# BrauV2_IOController.net
KiCad netlist of a schematic drawn in Altium Designer
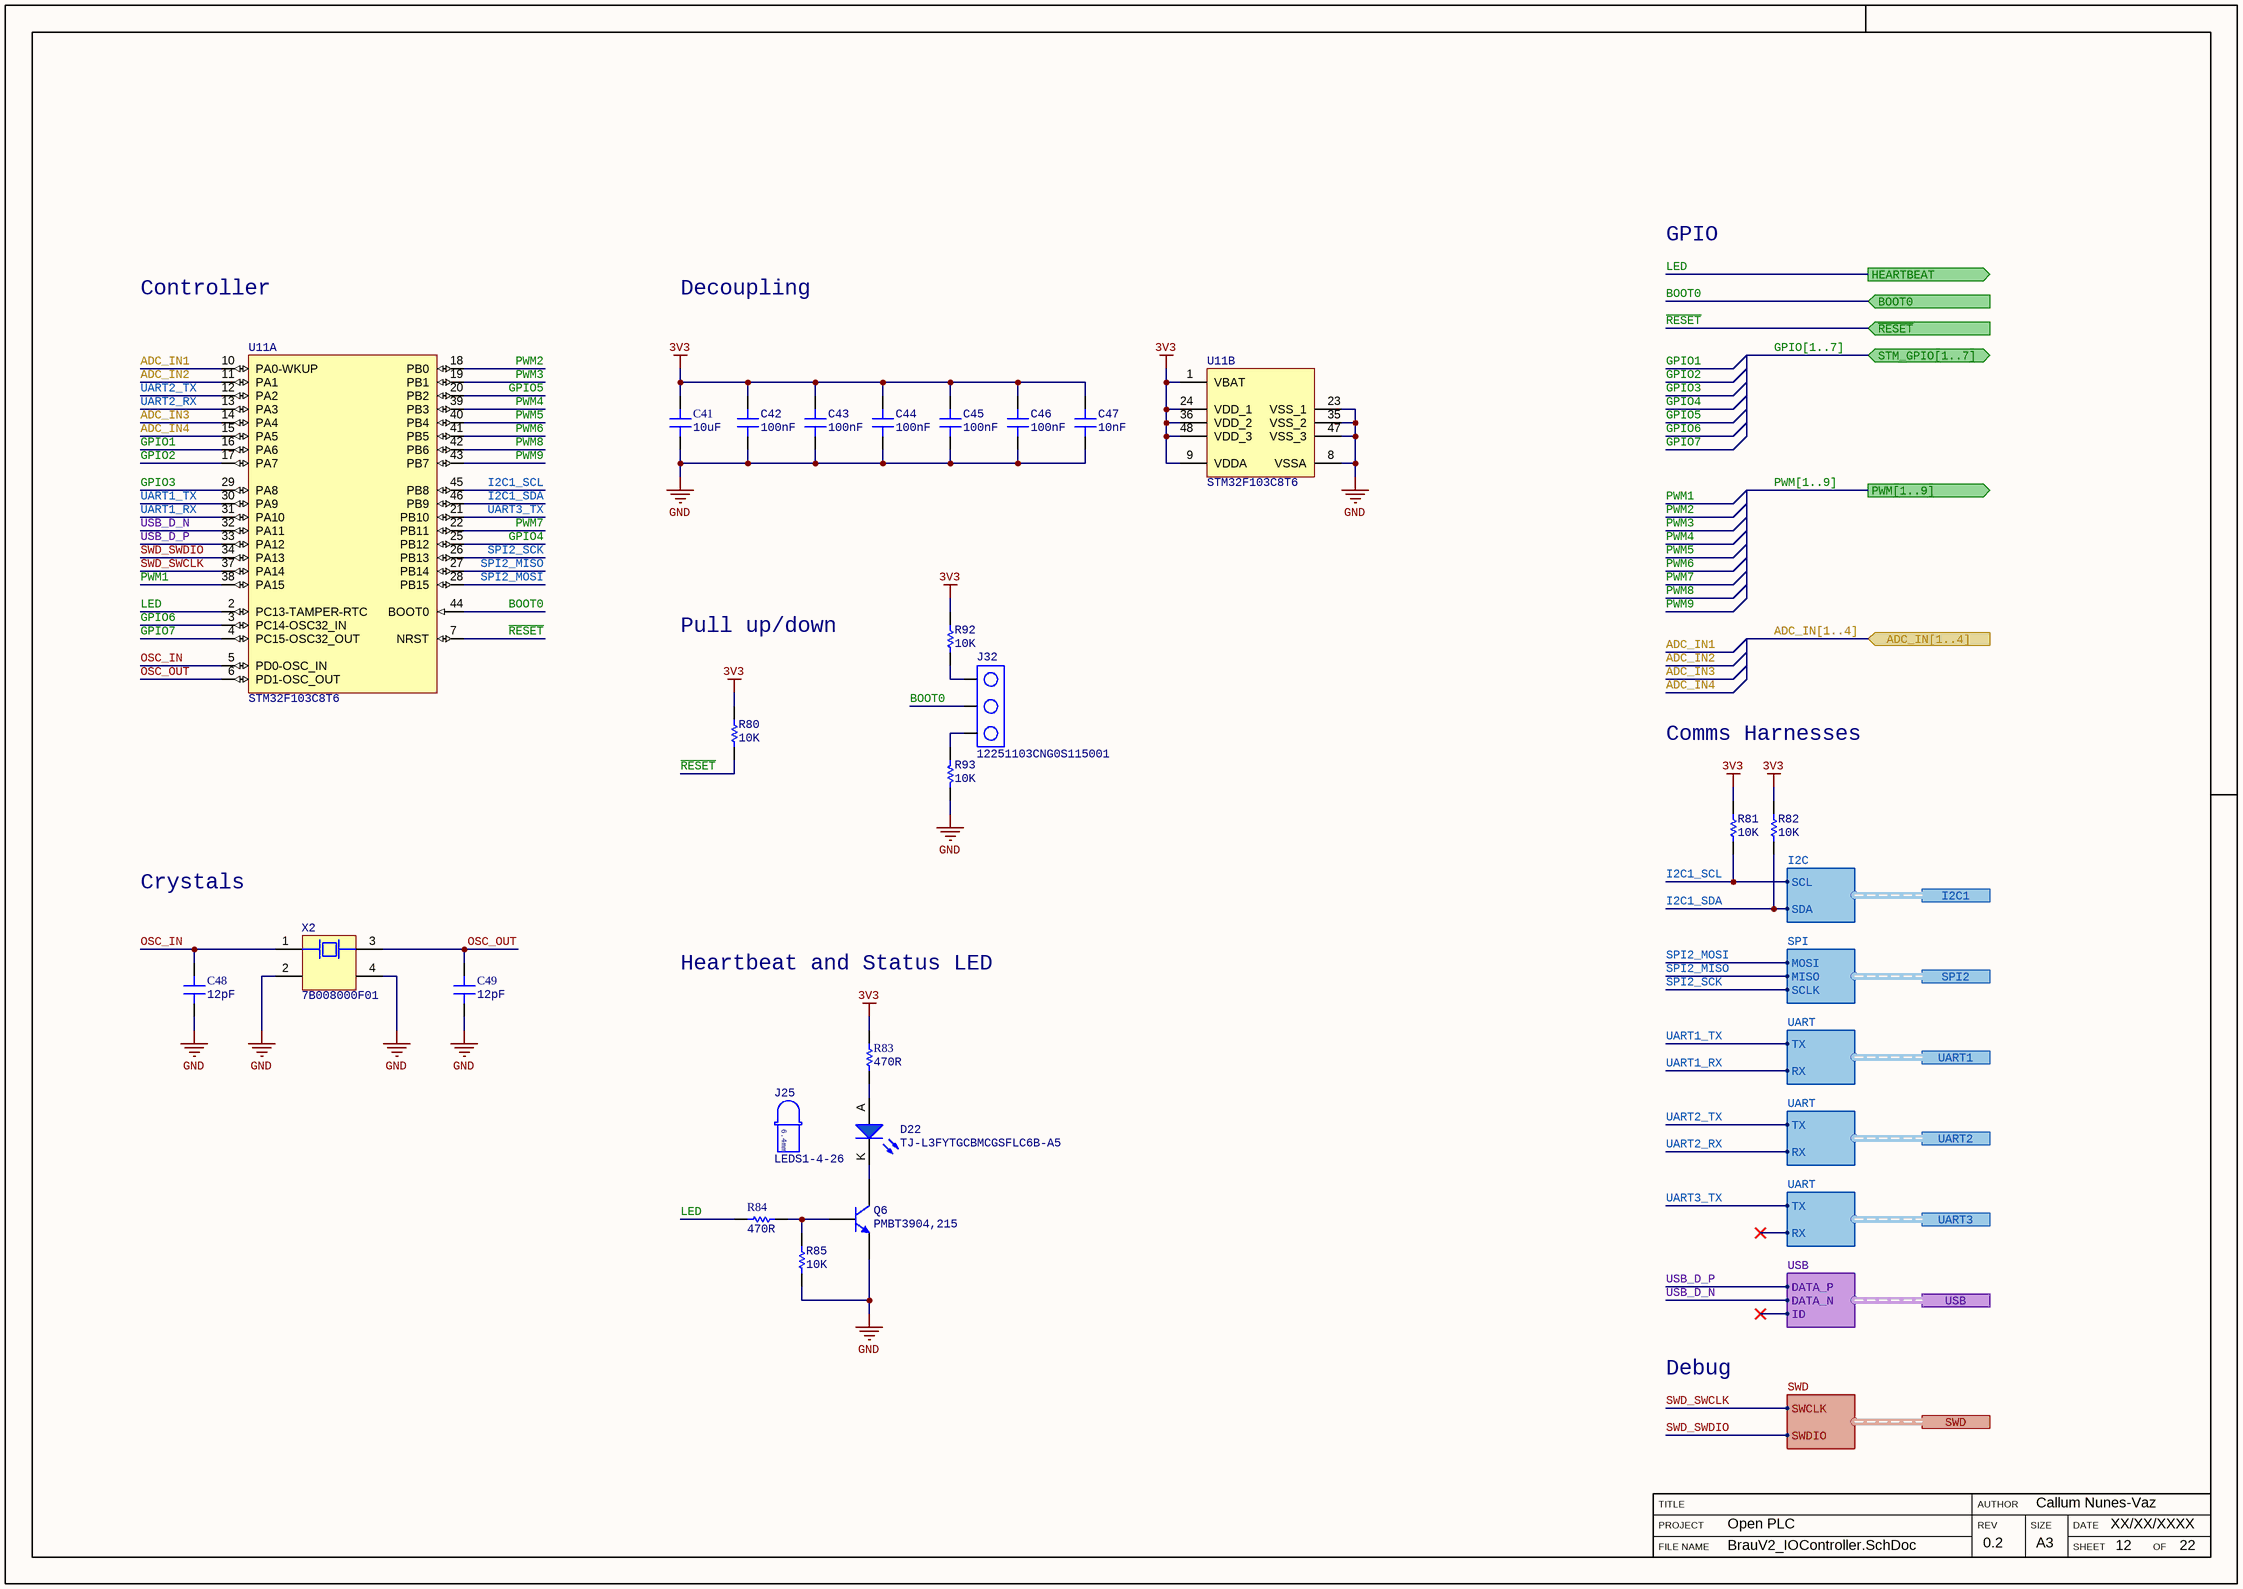
[diagram p0: BrauV2_IOController.SchDoc]

(export (version "E")
  (design (tool "Eeschema 10.0.6"))
  (components
    (comp (ref "C41")
      (value "CC1206KKX5R9BB106")
      (footprint "SMD_CAP_1206(3216)_N")
      (description "10uF ±10% 50V X5R 1206 Multilayer Ceramic Capacitors MLCC - SMD/SMT RoHS")
      (fields (field (name "TOLERANCE") "10%") (field (name "CAPACITANCE") "10uF"))
      (libsource (lib "BrauV2_Capacitor") (part "10uF 1206 50V 10%"))
    )
    (comp (ref "C42")
      (value "CC0402KRX5R6BB104")
      (footprint "SMD_CAP_0402(1005)_N")
      (description "100nF ±10% 10V X5R 0402 Multilayer Ceramic Capacitors MLCC - SMD/SMT RoHS")
      (fields (field (name "TOLERANCE") "10%") (field (name "CAPACITANCE") "100nF"))
      (libsource (lib "BrauV2_Capacitor") (part "100nF 0402 10V 10%"))
    )
    (comp (ref "C43")
      (value "CC0402KRX5R6BB104")
      (footprint "SMD_CAP_0402(1005)_N")
      (description "100nF ±10% 10V X5R 0402 Multilayer Ceramic Capacitors MLCC - SMD/SMT RoHS")
      (fields (field (name "TOLERANCE") "10%") (field (name "CAPACITANCE") "100nF"))
      (libsource (lib "BrauV2_Capacitor") (part "100nF 0402 10V 10%"))
    )
    (comp (ref "C44")
      (value "CC0402KRX5R6BB104")
      (footprint "SMD_CAP_0402(1005)_N")
      (description "100nF ±10% 10V X5R 0402 Multilayer Ceramic Capacitors MLCC - SMD/SMT RoHS")
      (fields (field (name "TOLERANCE") "10%") (field (name "CAPACITANCE") "100nF"))
      (libsource (lib "BrauV2_Capacitor") (part "100nF 0402 10V 10%"))
    )
    (comp (ref "C45")
      (value "CC0402KRX5R6BB104")
      (footprint "SMD_CAP_0402(1005)_N")
      (description "100nF ±10% 10V X5R 0402 Multilayer Ceramic Capacitors MLCC - SMD/SMT RoHS")
      (fields (field (name "TOLERANCE") "10%") (field (name "CAPACITANCE") "100nF"))
      (libsource (lib "BrauV2_Capacitor") (part "100nF 0402 10V 10%"))
    )
    (comp (ref "C46")
      (value "CC0402KRX5R6BB104")
      (footprint "SMD_CAP_0402(1005)_N")
      (description "100nF ±10% 10V X5R 0402 Multilayer Ceramic Capacitors MLCC - SMD/SMT RoHS")
      (fields (field (name "TOLERANCE") "10%") (field (name "CAPACITANCE") "100nF"))
      (libsource (lib "BrauV2_Capacitor") (part "100nF 0402 10V 10%"))
    )
    (comp (ref "C47")
      (value "CC0402KRX7R9BB103")
      (footprint "SMD_CAP_0402(1005)_N")
      (description "10nF ±10% 50V X7R 0402 Multilayer Ceramic Capacitors MLCC - SMD/SMT RoHS")
      (fields (field (name "TOLERANCE") "10%") (field (name "CAPACITANCE") "10nF"))
      (libsource (lib "BrauV2_Capacitor") (part "10nF 0402 50V 10%"))
    )
    (comp (ref "C48")
      (value "CC0402JRNPO9BN120")
      (footprint "SMD_CAP_0402(1005)_N")
      (description "12pF ±5% 50V NP0 0402 Multilayer Ceramic Capacitors MLCC - SMD/SMT RoHS")
      (fields (field (name "TOLERANCE") "5%") (field (name "CAPACITANCE") "12pF"))
      (libsource (lib "BrauV2_Capacitor") (part "12pF 0402 50V 5%"))
    )
    (comp (ref "C49")
      (value "CC0402JRNPO9BN120")
      (footprint "SMD_CAP_0402(1005)_N")
      (description "12pF ±5% 50V NP0 0402 Multilayer Ceramic Capacitors MLCC - SMD/SMT RoHS")
      (fields (field (name "TOLERANCE") "5%") (field (name "CAPACITANCE") "12pF"))
      (libsource (lib "BrauV2_Capacitor") (part "12pF 0402 50V 5%"))
    )
    (comp (ref "D22")
      (value "TJ-L3FYTGCBMCGSFLC6B-A5")
      (footprint "LED_3MM_SPACED_6.4MM_BLUE")
      (description "LED 3mm Blue 460nm~470nm 2.7V~3.6V Through Hole Light Emitting Diodes (LED) RoHS C330760")
      (libsource (lib "BrauV2_Diode") (part "TJ-L3FYTGCBMCGSFLC6B-A5"))
    )
    (comp (ref "J25")
      (value "LEDS1-4-26")
      (footprint "3MM_LED_SPACER_6.4MM")
      (description "3mm LED spacer 6.4mm height")
      (libsource (lib "BrauV2_Misc") (part "LEDS1-4-26"))
    )
    (comp (ref "J32")
      (value "12251103CNG0S115001")
      (footprint "Header_3POS")
      (description "Pin Header 3 1 right-angle，180degrees 2.54mm Through Hole,P=2.54mm Pin Header & Female Header RoHS")
      (libsource (lib "BrauV2_Connector") (part "3-way Jumper"))
    )
    (comp (ref "Q6")
      (value "PMBT3904,215")
      (footprint "SOT23-3")
      (description "NPN 200mA 40V 250mW SOT-23(SOT-23-3) Transistors (NPN/PNP) RoHS")
      (libsource (lib "BrauV2_Transistor") (part "PMBT3904,215"))
    )
    (comp (ref "R80")
      (value "RC0402FR-0710KL")
      (footprint "SMD_RES_0402(1005)_N")
      (description "10kΩ ±1% 1/16W ±100ppm/℃ 0402 Chip Resistor - Surface Mount RoHS")
      (fields (field (name "TOLERANCE") "1%") (field (name "RESISTANCE") "10K"))
      (libsource (lib "BrauV2_Resistor") (part "10K 0402 1% 1/16W"))
    )
    (comp (ref "R81")
      (value "RC0402FR-0710KL")
      (footprint "SMD_RES_0402(1005)_N")
      (description "10kΩ ±1% 1/16W ±100ppm/℃ 0402 Chip Resistor - Surface Mount RoHS")
      (fields (field (name "TOLERANCE") "1%") (field (name "RESISTANCE") "10K"))
      (libsource (lib "BrauV2_Resistor") (part "10K 0402 1% 1/16W"))
    )
    (comp (ref "R82")
      (value "RC0402FR-0710KL")
      (footprint "SMD_RES_0402(1005)_N")
      (description "10kΩ ±1% 1/16W ±100ppm/℃ 0402 Chip Resistor - Surface Mount RoHS")
      (fields (field (name "TOLERANCE") "1%") (field (name "RESISTANCE") "10K"))
      (libsource (lib "BrauV2_Resistor") (part "10K 0402 1% 1/16W"))
    )
    (comp (ref "R83")
      (value "RC0402FR-07470RL")
      (footprint "SMD_RES_0402(1005)_N")
      (description "470Ω ±1% 1/16W ±100ppm/℃ 0402 Chip Resistor - Surface Mount RoHS")
      (fields (field (name "TOLERANCE") "1%") (field (name "RESISTANCE") "470R"))
      (libsource (lib "BrauV2_Resistor") (part "470R 0402 1% 1W"))
    )
    (comp (ref "R84")
      (value "RC0402FR-07470RL")
      (footprint "SMD_RES_0402(1005)_N")
      (description "470Ω ±1% 1/16W ±100ppm/℃ 0402 Chip Resistor - Surface Mount RoHS")
      (fields (field (name "TOLERANCE") "1%") (field (name "RESISTANCE") "470R"))
      (libsource (lib "BrauV2_Resistor") (part "470R 0402 1% 1W"))
    )
    (comp (ref "R85")
      (value "RC0402FR-0710KL")
      (footprint "SMD_RES_0402(1005)_N")
      (description "10kΩ ±1% 1/16W ±100ppm/℃ 0402 Chip Resistor - Surface Mount RoHS")
      (fields (field (name "TOLERANCE") "1%") (field (name "RESISTANCE") "10K"))
      (libsource (lib "BrauV2_Resistor") (part "10K 0402 1% 1/16W"))
    )
    (comp (ref "R92")
      (value "RC0402FR-0710KL")
      (footprint "SMD_RES_0402(1005)_N")
      (description "10kΩ ±1% 1/16W ±100ppm/℃ 0402 Chip Resistor - Surface Mount RoHS")
      (fields (field (name "TOLERANCE") "1%") (field (name "RESISTANCE") "10K"))
      (libsource (lib "BrauV2_Resistor") (part "10K 0402 1% 1/16W"))
    )
    (comp (ref "R93")
      (value "RC0402FR-0710KL")
      (footprint "SMD_RES_0402(1005)_N")
      (description "10kΩ ±1% 1/16W ±100ppm/℃ 0402 Chip Resistor - Surface Mount RoHS")
      (fields (field (name "TOLERANCE") "1%") (field (name "RESISTANCE") "10K"))
      (libsource (lib "BrauV2_Resistor") (part "10K 0402 1% 1/16W"))
    )
    (comp (ref "U11")
      (value "STM32F103C8T6")
      (footprint "LQFP32_7x7")
      (libsource (lib "BrauV2_IC") (part "STM32F103C8T6"))
    )
    (comp (ref "X2")
      (value "7B008000F01")
      (footprint "CRYSTAL_3225")
      (description "8MHz ±10ppm 8pF 200Ω SMD-3225_4P SMD Crystal Resonators RoHS")
      (libsource (lib "BrauV2_Misc") (part "7B008000F01"))
    )
  )
  (nets
    (net (code "6") (name "/ADC_IN1") (class "Default")
      (node (ref "U11") (pin "10") (pinfunction "PA0-WKUP_10") (pintype "bidirectional"))
    )
    (net (code "7") (name "/ADC_IN2") (class "Default")
      (node (ref "U11") (pin "11") (pinfunction "PA1_11") (pintype "bidirectional"))
    )
    (net (code "8") (name "/ADC_IN3") (class "Default")
      (node (ref "U11") (pin "14") (pinfunction "PA4_14") (pintype "bidirectional"))
    )
    (net (code "9") (name "/ADC_IN4") (class "Default")
      (node (ref "U11") (pin "15") (pinfunction "PA5_15") (pintype "bidirectional"))
    )
    (net (code "11") (name "/BOOT0") (class "Default")
      (node (ref "J32") (pin "2") (pinfunction "2_2") (pintype "passive"))
      (node (ref "U11") (pin "44") (pinfunction "BOOT0_44") (pintype "input"))
    )
    (net (code "12") (name "/GPIO1") (class "Default")
      (node (ref "U11") (pin "16") (pinfunction "PA6_16") (pintype "bidirectional"))
    )
    (net (code "13") (name "/GPIO2") (class "Default")
      (node (ref "U11") (pin "17") (pinfunction "PA7_17") (pintype "bidirectional"))
    )
    (net (code "14") (name "/GPIO3") (class "Default")
      (node (ref "U11") (pin "29") (pinfunction "PA8_29") (pintype "bidirectional"))
    )
    (net (code "15") (name "/GPIO4") (class "Default")
      (node (ref "U11") (pin "25") (pinfunction "PB12_25") (pintype "bidirectional"))
    )
    (net (code "16") (name "/GPIO5") (class "Default")
      (node (ref "U11") (pin "20") (pinfunction "PB2_20") (pintype "bidirectional"))
    )
    (net (code "17") (name "/GPIO6") (class "Default")
      (node (ref "U11") (pin "3") (pinfunction "PC14-OSC32_IN_3") (pintype "bidirectional"))
    )
    (net (code "18") (name "/GPIO7") (class "Default")
      (node (ref "U11") (pin "4") (pinfunction "PC15-OSC32_OUT_4") (pintype "bidirectional"))
    )
    (net (code "20") (name "/I2C1_SCL") (class "Default")
      (node (ref "R81") (pin "1") (pinfunction "1_1") (pintype "passive"))
      (node (ref "U11") (pin "45") (pinfunction "PB8_45") (pintype "bidirectional"))
    )
    (net (code "21") (name "/I2C1_SDA") (class "Default")
      (node (ref "R82") (pin "1") (pinfunction "1_1") (pintype "passive"))
      (node (ref "U11") (pin "46") (pinfunction "PB9_46") (pintype "bidirectional"))
    )
    (net (code "22") (name "/LED") (class "Default")
      (node (ref "R84") (pin "2") (pinfunction "2_2") (pintype "passive"))
      (node (ref "U11") (pin "2") (pinfunction "PC13-TAMPER-RTC_2") (pintype "bidirectional"))
    )
    (net (code "23") (name "/OSC_IN") (class "Default")
      (node (ref "C48") (pin "2") (pinfunction "2_2") (pintype "passive"))
      (node (ref "U11") (pin "5") (pinfunction "PD0-OSC_IN_5") (pintype "bidirectional"))
      (node (ref "X2") (pin "1") (pinfunction "1_1") (pintype "passive"))
    )
    (net (code "24") (name "/OSC_OUT") (class "Default")
      (node (ref "C49") (pin "2") (pinfunction "2_2") (pintype "passive"))
      (node (ref "U11") (pin "6") (pinfunction "PD1-OSC_OUT_6") (pintype "bidirectional"))
      (node (ref "X2") (pin "3") (pinfunction "3_3") (pintype "passive"))
    )
    (net (code "25") (name "/PWM1") (class "Default")
      (node (ref "U11") (pin "38") (pinfunction "PA15_38") (pintype "bidirectional"))
    )
    (net (code "26") (name "/PWM2") (class "Default")
      (node (ref "U11") (pin "18") (pinfunction "PB0_18") (pintype "bidirectional"))
    )
    (net (code "27") (name "/PWM3") (class "Default")
      (node (ref "U11") (pin "19") (pinfunction "PB1_19") (pintype "bidirectional"))
    )
    (net (code "28") (name "/PWM4") (class "Default")
      (node (ref "U11") (pin "39") (pinfunction "PB3_39") (pintype "bidirectional"))
    )
    (net (code "29") (name "/PWM5") (class "Default")
      (node (ref "U11") (pin "40") (pinfunction "PB4_40") (pintype "bidirectional"))
    )
    (net (code "30") (name "/PWM6") (class "Default")
      (node (ref "U11") (pin "41") (pinfunction "PB5_41") (pintype "bidirectional"))
    )
    (net (code "31") (name "/PWM7") (class "Default")
      (node (ref "U11") (pin "22") (pinfunction "PB11_22") (pintype "bidirectional"))
    )
    (net (code "32") (name "/PWM8") (class "Default")
      (node (ref "U11") (pin "42") (pinfunction "PB6_42") (pintype "bidirectional"))
    )
    (net (code "33") (name "/PWM9") (class "Default")
      (node (ref "U11") (pin "43") (pinfunction "PB7_43") (pintype "bidirectional"))
    )
    (net (code "35") (name "/SPI2_MISO") (class "Default")
      (node (ref "U11") (pin "27") (pinfunction "PB14_27") (pintype "bidirectional"))
    )
    (net (code "36") (name "/SPI2_MOSI") (class "Default")
      (node (ref "U11") (pin "28") (pinfunction "PB15_28") (pintype "bidirectional"))
    )
    (net (code "37") (name "/SPI2_SCK") (class "Default")
      (node (ref "U11") (pin "26") (pinfunction "PB13_26") (pintype "bidirectional"))
    )
    (net (code "38") (name "/SWD_SWCLK") (class "Default")
      (node (ref "U11") (pin "37") (pinfunction "PA14_37") (pintype "bidirectional"))
    )
    (net (code "39") (name "/SWD_SWDIO") (class "Default")
      (node (ref "U11") (pin "34") (pinfunction "PA13_34") (pintype "bidirectional"))
    )
    (net (code "40") (name "/UART1_RX") (class "Default")
      (node (ref "U11") (pin "31") (pinfunction "PA10_31") (pintype "bidirectional"))
    )
    (net (code "41") (name "/UART1_TX") (class "Default")
      (node (ref "U11") (pin "30") (pinfunction "PA9_30") (pintype "bidirectional"))
    )
    (net (code "42") (name "/UART2_RX") (class "Default")
      (node (ref "U11") (pin "13") (pinfunction "PA3_13") (pintype "bidirectional"))
    )
    (net (code "43") (name "/UART2_TX") (class "Default")
      (node (ref "U11") (pin "12") (pinfunction "PA2_12") (pintype "bidirectional"))
    )
    (net (code "44") (name "/UART3_TX") (class "Default")
      (node (ref "U11") (pin "21") (pinfunction "PB10_21") (pintype "bidirectional"))
    )
    (net (code "45") (name "/USB_D_N") (class "Default")
      (node (ref "U11") (pin "32") (pinfunction "PA11_32") (pintype "bidirectional"))
    )
    (net (code "46") (name "/USB_D_P") (class "Default")
      (node (ref "U11") (pin "33") (pinfunction "PA12_33") (pintype "bidirectional"))
    )
    (net (code "52") (name "/~{RESET}") (class "Default")
      (node (ref "R80") (pin "1") (pinfunction "1_1") (pintype "passive"))
      (node (ref "U11") (pin "7") (pinfunction "NRST_7") (pintype "bidirectional"))
    )
    (net (code "53") (name "3V3") (class "Default")
      (node (ref "C41") (pin "2") (pinfunction "2_2") (pintype "passive"))
      (node (ref "C42") (pin "2") (pinfunction "2_2") (pintype "passive"))
      (node (ref "C43") (pin "2") (pinfunction "2_2") (pintype "passive"))
      (node (ref "C44") (pin "2") (pinfunction "2_2") (pintype "passive"))
      (node (ref "C45") (pin "2") (pinfunction "2_2") (pintype "passive"))
      (node (ref "C46") (pin "2") (pinfunction "2_2") (pintype "passive"))
      (node (ref "C47") (pin "2") (pinfunction "2_2") (pintype "passive"))
      (node (ref "R80") (pin "2") (pinfunction "2_2") (pintype "passive"))
      (node (ref "R81") (pin "2") (pinfunction "2_2") (pintype "passive"))
      (node (ref "R82") (pin "2") (pinfunction "2_2") (pintype "passive"))
      (node (ref "R83") (pin "1") (pinfunction "1_1") (pintype "passive"))
      (node (ref "R92") (pin "2") (pinfunction "2_2") (pintype "passive"))
      (node (ref "U11") (pin "1") (pinfunction "VBAT_1") (pintype "power_in"))
      (node (ref "U11") (pin "24") (pinfunction "VDD_1_24") (pintype "power_in"))
      (node (ref "U11") (pin "36") (pinfunction "VDD_2_36") (pintype "power_in"))
      (node (ref "U11") (pin "48") (pinfunction "VDD_3_48") (pintype "power_in"))
      (node (ref "U11") (pin "9") (pinfunction "VDDA_9") (pintype "power_in"))
    )
    (net (code "54") (name "GND") (class "Default")
      (node (ref "C41") (pin "1") (pinfunction "1_1") (pintype "passive"))
      (node (ref "C42") (pin "1") (pinfunction "1_1") (pintype "passive"))
      (node (ref "C43") (pin "1") (pinfunction "1_1") (pintype "passive"))
      (node (ref "C44") (pin "1") (pinfunction "1_1") (pintype "passive"))
      (node (ref "C45") (pin "1") (pinfunction "1_1") (pintype "passive"))
      (node (ref "C46") (pin "1") (pinfunction "1_1") (pintype "passive"))
      (node (ref "C47") (pin "1") (pinfunction "1_1") (pintype "passive"))
      (node (ref "C48") (pin "1") (pinfunction "1_1") (pintype "passive"))
      (node (ref "C49") (pin "1") (pinfunction "1_1") (pintype "passive"))
      (node (ref "Q6") (pin "2") (pinfunction "E_2") (pintype "passive"))
      (node (ref "R85") (pin "1") (pinfunction "1_1") (pintype "passive"))
      (node (ref "R93") (pin "2") (pinfunction "2_2") (pintype "passive"))
      (node (ref "U11") (pin "23") (pinfunction "VSS_1_23") (pintype "power_in"))
      (node (ref "U11") (pin "35") (pinfunction "VSS_2_35") (pintype "power_in"))
      (node (ref "U11") (pin "47") (pinfunction "VSS_3_47") (pintype "power_in"))
      (node (ref "U11") (pin "8") (pinfunction "VSSA_8") (pintype "power_in"))
      (node (ref "X2") (pin "2") (pinfunction "2_2") (pintype "passive"))
      (node (ref "X2") (pin "4") (pinfunction "4_4") (pintype "passive"))
    )
    (net (code "55") (name "Net-(D22-PadA)") (class "Default")
      (node (ref "D22") (pin "A") (pinfunction "A_A") (pintype "passive"))
      (node (ref "R83") (pin "2") (pinfunction "2_2") (pintype "passive"))
    )
    (net (code "56") (name "Net-(J32-Pad1)") (class "Default")
      (node (ref "J32") (pin "1") (pinfunction "1_1") (pintype "passive"))
      (node (ref "R92") (pin "1") (pinfunction "1_1") (pintype "passive"))
    )
    (net (code "57") (name "Net-(J32-Pad3)") (class "Default")
      (node (ref "J32") (pin "3") (pinfunction "3_3") (pintype "passive"))
      (node (ref "R93") (pin "1") (pinfunction "1_1") (pintype "passive"))
    )
    (net (code "58") (name "Net-(Q6-B)") (class "Default")
      (node (ref "Q6") (pin "1") (pinfunction "B_1") (pintype "passive"))
      (node (ref "R84") (pin "1") (pinfunction "1_1") (pintype "passive"))
      (node (ref "R85") (pin "2") (pinfunction "2_2") (pintype "passive"))
    )
    (net (code "59") (name "Net-(Q6-C)") (class "Default")
      (node (ref "D22") (pin "K") (pinfunction "K_K") (pintype "passive"))
      (node (ref "Q6") (pin "3") (pinfunction "C_3") (pintype "passive"))
    )
  )
)
